# P24_AUDIO.net
KiCad netlist of a schematic drawn in Altium Designer
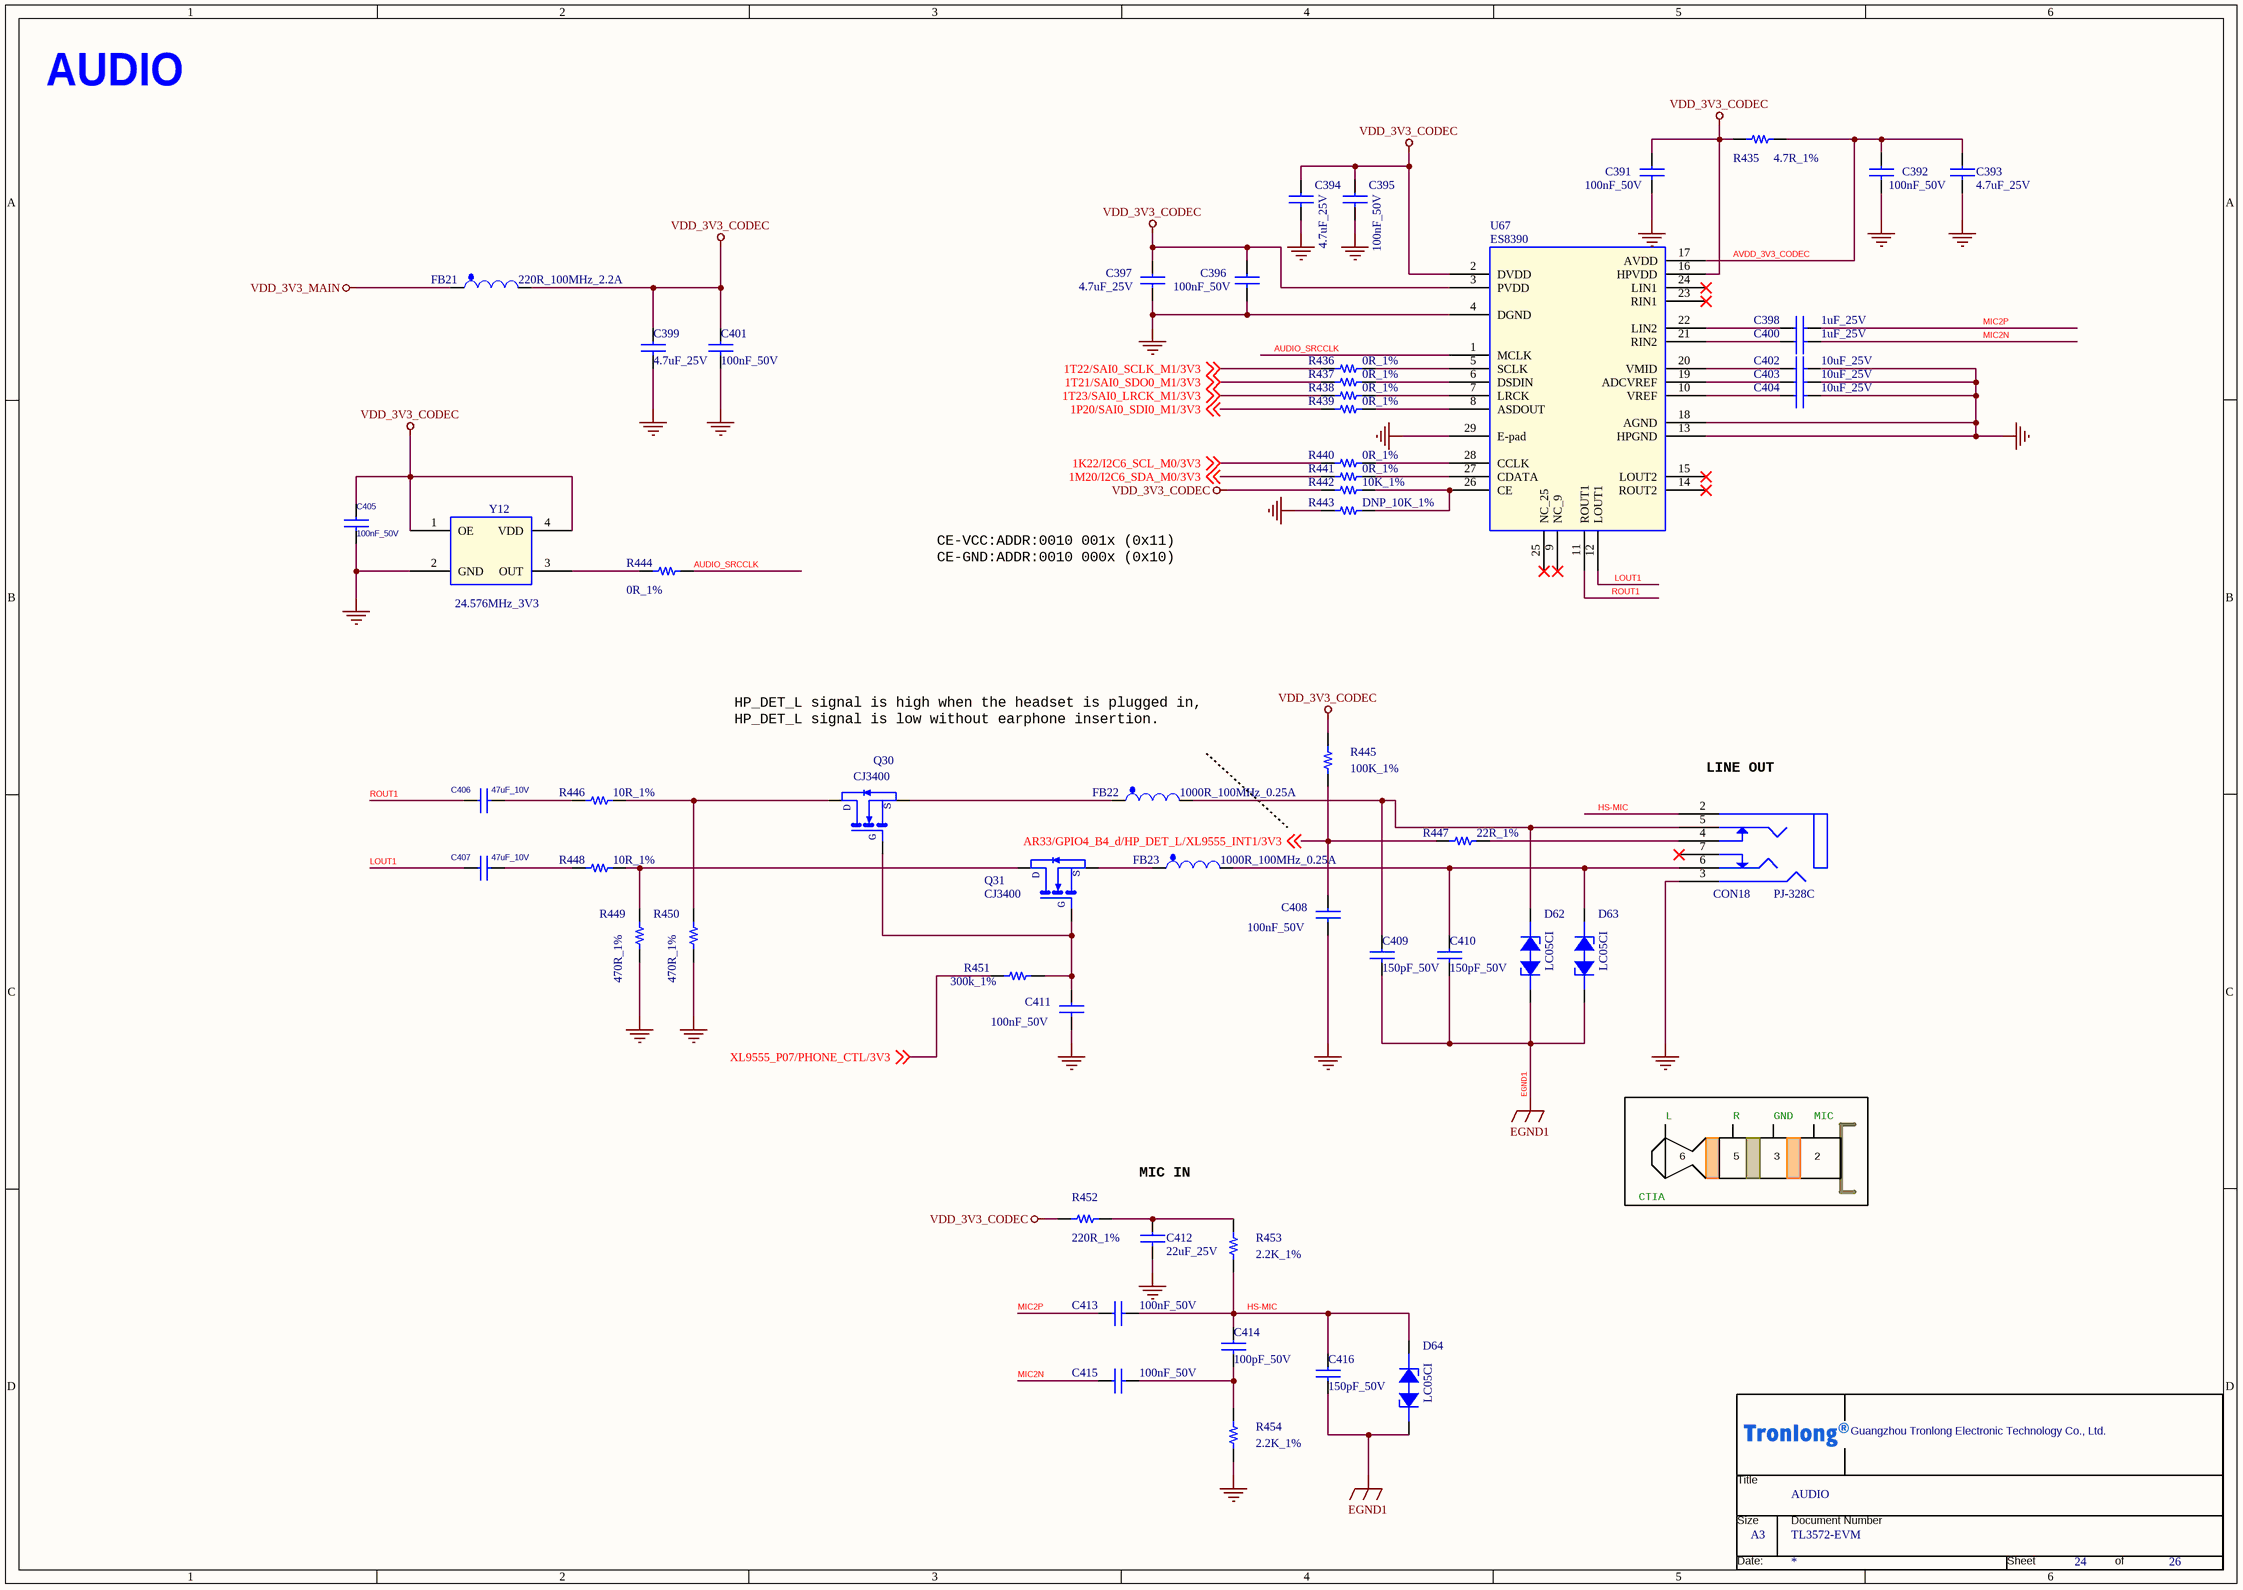
[diagram p0: P24_AUDIO.SchDoc]

(export (version "E")
  (design (tool "Eeschema 10.0.6"))
  (components
    (comp (ref "*")
      (value "TL_NEW")
      (fields
        (field (name "PAGE COUNT") "26")
        (field (name "PAGE NUMBER") "24")
        (field (name "PAGE SIZE") "A3")
        (field (name "ORGNAME") "Guangzhou Tronlong Electronic Technology Co., Ltd.")
        (field (name "TITLE") "AUDIO")
        (field (name "DOC") "TL3572-EVM")
      )
      (libsource (lib "*") (part "TL_NEW"))
    )
    (comp (ref "C391")
      (value "100nF_50V")
      (footprint "C0402")
      (description "贴片陶瓷电容,100nF,10%,50V,X7R")
      (fields
        (field (name "MANUFACTURER") "广东风华高新科技股份有限公司（FH）")
        (field (name "MANUFACTURER PARTNUMBER") "0402B104K500NT")
      )
      (libsource (lib "*") (part "CAP NP_Dup3"))
    )
    (comp (ref "C392")
      (value "100nF_50V")
      (footprint "C0402")
      (description "贴片陶瓷电容,100nF,10%,50V,X7R")
      (fields
        (field (name "MANUFACTURER PARTNUMBER") "0402B104K500NT")
        (field (name "MANUFACTURER") "广东风华高新科技股份有限公司（FH）")
      )
      (libsource (lib "*") (part "CAP NP_Dup3"))
    )
    (comp (ref "C393")
      (value "4.7uF_25V")
      (footprint "C0603")
      (description "贴片陶瓷电容,4.7uF,10%,25V,X5R")
      (fields
        (field (name "MANUFACTURER") "广东风华高新科技股份有限公司（FH）")
        (field (name "MANUFACTURER PARTNUMBER") "0603X475K250NT")
      )
      (libsource (lib "*") (part "CAP NP_Dup3"))
    )
    (comp (ref "C394")
      (value "4.7uF_25V")
      (footprint "C0603")
      (description "贴片陶瓷电容,4.7uF,10%,25V,X5R")
      (fields
        (field (name "MANUFACTURER") "广东风华高新科技股份有限公司（FH）")
        (field (name "MANUFACTURER PARTNUMBER") "0603X475K250NT")
      )
      (libsource (lib "*") (part "CAP NP_Dup3"))
    )
    (comp (ref "C395")
      (value "100nF_50V")
      (footprint "C0402")
      (description "贴片陶瓷电容,100nF,10%,50V,X7R")
      (fields
        (field (name "MANUFACTURER PARTNUMBER") "0402B104K500NT")
        (field (name "MANUFACTURER") "广东风华高新科技股份有限公司（FH）")
      )
      (libsource (lib "*") (part "CAP NP_Dup3"))
    )
    (comp (ref "C396")
      (value "100nF_50V")
      (footprint "C0402")
      (description "贴片陶瓷电容,100nF,10%,50V,X7R")
      (fields
        (field (name "MANUFACTURER") "广东风华高新科技股份有限公司（FH）")
        (field (name "MANUFACTURER PARTNUMBER") "0402B104K500NT")
      )
      (libsource (lib "*") (part "CAP NP_Dup3"))
    )
    (comp (ref "C397")
      (value "4.7uF_25V")
      (footprint "C0603")
      (description "贴片陶瓷电容,4.7uF,10%,25V,X5R")
      (fields
        (field (name "MANUFACTURER") "广东风华高新科技股份有限公司（FH）")
        (field (name "MANUFACTURER PARTNUMBER") "0603X475K250NT")
      )
      (libsource (lib "*") (part "CAP NP_Dup3"))
    )
    (comp (ref "C398")
      (value "1uF_25V")
      (footprint "C0402")
      (description "贴片陶瓷电容,1uF,10%,25V,X5R")
      (fields
        (field (name "MANUFACTURER PARTNUMBER") "0402X105K250NT")
        (field (name "MANUFACTURER") "广东风华高新科技股份有限公司（FH）")
      )
      (libsource (lib "*") (part "CAP NP_Dup3"))
    )
    (comp (ref "C399")
      (value "4.7uF_25V")
      (footprint "C0603")
      (description "贴片陶瓷电容,4.7uF,10%,25V,X5R")
      (fields
        (field (name "MANUFACTURER PARTNUMBER") "0603X475K250NT")
        (field (name "MANUFACTURER") "广东风华高新科技股份有限公司（FH）")
      )
      (libsource (lib "*") (part "CAP NP_Dup3"))
    )
    (comp (ref "C400")
      (value "1uF_25V")
      (footprint "C0402")
      (description "贴片陶瓷电容,1uF,10%,25V,X5R")
      (fields
        (field (name "MANUFACTURER PARTNUMBER") "0402X105K250NT")
        (field (name "MANUFACTURER") "广东风华高新科技股份有限公司（FH）")
      )
      (libsource (lib "*") (part "CAP NP_Dup3"))
    )
    (comp (ref "C401")
      (value "100nF_50V")
      (footprint "C0402")
      (description "贴片陶瓷电容,100nF,10%,50V,X7R")
      (fields
        (field (name "MANUFACTURER PARTNUMBER") "0402B104K500NT")
        (field (name "MANUFACTURER") "广东风华高新科技股份有限公司（FH）")
      )
      (libsource (lib "*") (part "CAP NP_Dup3"))
    )
    (comp (ref "C402")
      (value "10uF_25V")
      (footprint "C0603")
      (description "贴片陶瓷电容,10uF,20%,25V,X5R")
      (fields
        (field (name "MANUFACTURER PARTNUMBER") "0603X106M250NT")
        (field (name "MANUFACTURER") "广东风华高新科技股份有限公司（FH）")
      )
      (libsource (lib "*") (part "CAP NP_Dup3"))
    )
    (comp (ref "C403")
      (value "10uF_25V")
      (footprint "C0603")
      (description "贴片陶瓷电容,10uF,20%,25V,X5R")
      (fields
        (field (name "MANUFACTURER PARTNUMBER") "0603X106M250NT")
        (field (name "MANUFACTURER") "广东风华高新科技股份有限公司（FH）")
      )
      (libsource (lib "*") (part "CAP NP_Dup3"))
    )
    (comp (ref "C404")
      (value "10uF_25V")
      (footprint "C0603")
      (description "贴片陶瓷电容,10uF,20%,25V,X5R")
      (fields
        (field (name "MANUFACTURER") "广东风华高新科技股份有限公司（FH）")
        (field (name "MANUFACTURER PARTNUMBER") "0603X106M250NT")
      )
      (libsource (lib "*") (part "CAP NP_Dup3"))
    )
    (comp (ref "C405")
      (value "100nF_50V")
      (footprint "C0402")
      (description "贴片陶瓷电容,100nF,10%,50V,X7R")
      (fields
        (field (name "MANUFACTURER") "广东风华高新科技股份有限公司（FH）")
        (field (name "MANUFACTURER PARTNUMBER") "0402B104K500NT")
      )
      (libsource (lib "*") (part "CAP NP_Dup2"))
    )
    (comp (ref "C406")
      (value "47uF_10V")
      (footprint "C0805")
      (description "贴片陶瓷电容,47uF,20%,10V,X5R")
      (fields
        (field (name "MANUFACTURER PARTNUMBER") "0805X476M100NT")
        (field (name "MANUFACTURER") "广东风华高新科技股份有限公司（FH）")
      )
      (libsource (lib "*") (part "CAP NP_Dup3"))
    )
    (comp (ref "C407")
      (value "47uF_10V")
      (footprint "C0805")
      (description "贴片陶瓷电容,47uF,20%,10V,X5R")
      (fields
        (field (name "MANUFACTURER PARTNUMBER") "0805X476M100NT")
        (field (name "MANUFACTURER") "广东风华高新科技股份有限公司（FH）")
      )
      (libsource (lib "*") (part "CAP NP_Dup3"))
    )
    (comp (ref "C408")
      (value "100nF_50V")
      (footprint "C0402")
      (description "贴片陶瓷电容,100nF,10%,50V,X7R")
      (fields
        (field (name "MANUFACTURER PARTNUMBER") "0402B104K500NT")
        (field (name "MANUFACTURER") "广东风华高新科技股份有限公司（FH）")
      )
      (libsource (lib "*") (part "CAP NP_Dup3"))
    )
    (comp (ref "C409")
      (value "150pF_50V")
      (footprint "C0603")
      (description "贴片陶瓷电容,150pF,5%,50V,COG")
      (fields
        (field (name "MANUFACTURER") "广东风华高新科技股份有限公司（FH）")
        (field (name "MANUFACTURER PARTNUMBER") "0603CG151J500NT")
      )
      (libsource (lib "*") (part "CAP NP_Dup2"))
    )
    (comp (ref "C410")
      (value "150pF_50V")
      (footprint "C0603")
      (description "贴片陶瓷电容,150pF,5%,50V,COG")
      (fields
        (field (name "MANUFACTURER PARTNUMBER") "0603CG151J500NT")
        (field (name "MANUFACTURER") "广东风华高新科技股份有限公司（FH）")
      )
      (libsource (lib "*") (part "CAP NP_Dup2"))
    )
    (comp (ref "C411")
      (value "100nF_50V")
      (footprint "C0402")
      (description "贴片陶瓷电容,100nF,10%,50V,X7R")
      (fields
        (field (name "MANUFACTURER PARTNUMBER") "0402B104K500NT")
        (field (name "MANUFACTURER") "广东风华高新科技股份有限公司（FH）")
      )
      (libsource (lib "*") (part "CAP NP_Dup3"))
    )
    (comp (ref "C412")
      (value "22uF_25V")
      (footprint "C0805")
      (description "贴片陶瓷电容,22uF,20%,25V,X5R")
      (fields
        (field (name "MANUFACTURER") "广东风华高新科技股份有限公司（FH）")
        (field (name "MANUFACTURER PARTNUMBER") "0805X226M250NT")
      )
      (libsource (lib "*") (part "CAP NP_Dup3"))
    )
    (comp (ref "C413")
      (value "100nF_50V")
      (footprint "C0402")
      (description "贴片陶瓷电容,100nF,10%,50V,X7R")
      (fields
        (field (name "VOLTAGE") "50V")
        (field (name "TOLERANCE") "10%")
        (field (name "CREATED BY") "JJJ")
      )
      (libsource (lib "*") (part "CAP NP_Dup3"))
    )
    (comp (ref "C414")
      (value "100pF_50V")
      (footprint "C0402")
      (description "贴片陶瓷电容,100pF,5%,50V,COG")
      (fields
        (field (name "MANUFACTURER PARTNUMBER") "0402CG101J500NT")
        (field (name "MANUFACTURER") "广东风华高新科技股份有限公司（FH）")
        (field (name "CREATED BY") "JJJ")
      )
      (libsource (lib "*") (part "CAP NP_Dup3"))
    )
    (comp (ref "C415")
      (value "100nF_50V")
      (footprint "C0402")
      (description "贴片陶瓷电容,100nF,10%,50V,X7R")
      (fields
        (field (name "VOLTAGE") "50V")
        (field (name "TOLERANCE") "10%")
        (field (name "CREATED BY") "JJJ")
      )
      (libsource (lib "*") (part "CAP NP_Dup3"))
    )
    (comp (ref "C416")
      (value "150pF_50V")
      (footprint "C0603")
      (description "贴片陶瓷电容,150pF,5%,50V,COG")
      (fields
        (field (name "MANUFACTURER PARTNUMBER") "0603CG151J500NT")
        (field (name "MANUFACTURER") "广东风华高新科技股份有限公司（FH）")
      )
      (libsource (lib "*") (part "CAP NP_Dup2"))
    )
    (comp (ref "CON18")
      (value "PJ-328C")
      (footprint "PJ-328C")
      (description "插件音频连接器,孔径3.5mm,黑色")
      (fields (field (name "MANUFACTURER") "深圳市金航标电子有限公司(kinghelm)"))
      (libsource (lib "*") (part "PJ-328C_0"))
    )
    (comp (ref "D62")
      (value "LC05CI")
      (footprint "SOD323")
      (description "TVS二极管,VRWM=5V,VBR=6V,一组,双向,30KV,30KV")
      (fields (field (name "MANUFACTURER") "上海雷卯电子科技有限公司（Leiditech）"))
      (libsource (lib "*") (part "DIODE BREAKDOWN_2"))
    )
    (comp (ref "D63")
      (value "LC05CI")
      (footprint "SOD323")
      (description "TVS二极管,VRWM=5V,VBR=6V,一组,双向,30KV,30KV")
      (fields (field (name "MANUFACTURER") "上海雷卯电子科技有限公司（Leiditech）"))
      (libsource (lib "*") (part "DIODE BREAKDOWN_2"))
    )
    (comp (ref "D64")
      (value "LC05CI")
      (footprint "SOD323")
      (description "TVS二极管,VRWM=5V,VBR=6V,一组,双向,30KV,30KV")
      (fields (field (name "MANUFACTURER") "上海雷卯电子科技有限公司（Leiditech）"))
      (libsource (lib "*") (part "DIODE BREAKDOWN_2"))
    )
    (comp (ref "FB21")
      (value "220R_100MHz_2.2A")
      (footprint "L0603")
      (description "磁珠,50mΩ,2.2A,220R@100MHz")
      (fields
        (field (name "PART NUMBER") "647-01-3069")
        (field (name "MANUFACTURER PARTNUMBER") "UPZ1608U221-2R2TF")
      )
      (libsource (lib "*") (part "FB_0"))
    )
    (comp (ref "FB22")
      (value "1000R_100MHz_0.25A")
      (footprint "L0402")
      (description "磁珠,900mΩ,0.25A,1000R@100MHz")
      (fields
        (field (name "MANUFACTURER") "广东风华高新科技股份有限公司(FH)")
        (field (name "MANUFACTURER PARTNUMBER") "CBW100505U102T")
      )
      (libsource (lib "*") (part "FB_0"))
    )
    (comp (ref "FB23")
      (value "1000R_100MHz_0.25A")
      (footprint "L0402")
      (description "磁珠,900mΩ,0.25A,1000R@100MHz")
      (fields
        (field (name "PART NUMBER") "647-01-3069")
        (field (name "MANUFACTURER PARTNUMBER") "CBW100505U102T")
      )
      (libsource (lib "*") (part "FB_0"))
    )
    (comp (ref "Q30")
      (value "CJ3400")
      (footprint "SOT23-3")
      (description "MOSFET,N沟道,VDSS=30V,VGSS=±12V,ID=5.8A,PD=0.35W,VGS(th)=1.4V")
      (fields (field (name "MANUFACTURER") "江苏长晶科技股份有限公司（JSCJ）"))
      (libsource (lib "*") (part "MMBT3904/SOT_1"))
    )
    (comp (ref "Q31")
      (value "CJ3400")
      (footprint "SOT23-3")
      (description "MOSFET,N沟道,VDSS=30V,VGSS=±12V,ID=5.8A,PD=0.35W,VGS(th)=1.4V")
      (fields (field (name "MANUFACTURER") "江苏长晶科技股份有限公司（JSCJ）"))
      (libsource (lib "*") (part "MMBT3904/SOT_1"))
    )
    (comp (ref "R435")
      (value "4.7R_1%")
      (footprint "R0603")
      (description "/")
      (fields
        (field (name "MANUFACTURER PARTNUMBER") "4.7R,±1%,R0603,≥1/10W")
        (field (name "MANUFACTURER") "广州创龙")
      )
      (libsource (lib "*") (part "Resistor_Dup4"))
    )
    (comp (ref "R436")
      (value "0R_1%")
      (footprint "R0402")
      (description "贴片电阻,0R,±1%,1/16W")
      (fields
        (field (name "MANUFACTURER") "广东风华高新科技股份有限公司（FH）")
        (field (name "MANUFACTURER PARTNUMBER") "RC-02000FT")
      )
      (libsource (lib "*") (part "Resistor_Dup4"))
    )
    (comp (ref "R437")
      (value "0R_1%")
      (footprint "R0402")
      (description "贴片电阻,0R,±1%,1/16W")
      (fields
        (field (name "MANUFACTURER") "广东风华高新科技股份有限公司（FH）")
        (field (name "MANUFACTURER PARTNUMBER") "RC-02000FT")
      )
      (libsource (lib "*") (part "Resistor_Dup4"))
    )
    (comp (ref "R438")
      (value "0R_1%")
      (footprint "R0402")
      (description "贴片电阻,0R,±1%,1/16W")
      (fields (field (name "TOLERANCE") "5%") (field (name "MANUFACTURER PARTNUMBER") "RC-02000FT"))
      (libsource (lib "*") (part "Resistor_Dup4"))
    )
    (comp (ref "R439")
      (value "0R_1%")
      (footprint "R0402")
      (description "贴片电阻,0R,±1%,1/16W")
      (fields (field (name "TOLERANCE") "5%") (field (name "MANUFACTURER PARTNUMBER") "RC-02000FT"))
      (libsource (lib "*") (part "Resistor_Dup4"))
    )
    (comp (ref "R440")
      (value "0R_1%")
      (footprint "R0402")
      (description "贴片电阻,0R,±1%,1/16W")
      (fields (field (name "TOLERANCE") "5%") (field (name "MANUFACTURER PARTNUMBER") "RC-02000FT"))
      (libsource (lib "*") (part "Resistor_Dup4"))
    )
    (comp (ref "R441")
      (value "0R_1%")
      (footprint "R0402")
      (description "贴片电阻,0R,±1%,1/16W")
      (fields (field (name "TOLERANCE") "5%") (field (name "MANUFACTURER PARTNUMBER") "RC-02000FT"))
      (libsource (lib "*") (part "Resistor_Dup4"))
    )
    (comp (ref "R442")
      (value "10K_1%")
      (footprint "R0402")
      (description "贴片电阻,10K,±1%,1/16W")
      (fields
        (field (name "MANUFACTURER") "广东风华高新科技股份有限公司（FH）")
        (field (name "MANUFACTURER PARTNUMBER") "RC-02K1002FT")
      )
      (libsource (lib "*") (part "Resistor_Dup4"))
    )
    (comp (ref "R443")
      (value "DNP_10K_1%")
      (footprint "R0402")
      (description "贴片电阻,10K,±1%,1/16W")
      (fields (field (name "TOLERANCE") "5%") (field (name "MANUFACTURER PARTNUMBER") "RC-02K1002FT"))
      (libsource (lib "*") (part "Resistor_Dup4"))
    )
    (comp (ref "R444")
      (value "0R_1%")
      (footprint "R0603")
      (description "贴片电阻,0R,±1%,1/10W")
      (fields
        (field (name "MANUFACTURER") "广东风华高新科技股份有限公司（FH）")
        (field (name "MANUFACTURER PARTNUMBER") "RS-03000FT")
      )
      (libsource (lib "*") (part "Resistor_Dup3"))
    )
    (comp (ref "R445")
      (value "100K_1%")
      (footprint "R0402")
      (description "RC0402FR-07100KL,0402WGF1003TCE")
      (fields
        (field (name "MANUFACTURER") "广州创龙")
        (field (name "MANUFACTURER PARTNUMBER") "100K,±1%,R0402,≥1/16W")
      )
      (libsource (lib "*") (part "Resistor_Dup4"))
    )
    (comp (ref "R446")
      (value "10R_1%")
      (footprint "R0603")
      (description "贴片电阻,10R,±1%,1/10W")
      (fields
        (field (name "MANUFACTURER") "广东风华高新科技股份有限公司（FH）")
        (field (name "MANUFACTURER PARTNUMBER") "RS-03K10R0FT")
      )
      (libsource (lib "*") (part "Resistor_Dup4"))
    )
    (comp (ref "R447")
      (value "22R_1%")
      (footprint "R0402")
      (description "贴片电阻,22R,±1%,1/16W")
      (fields
        (field (name "MANUFACTURER") "广东风华高新科技股份有限公司（FH）")
        (field (name "MANUFACTURER PARTNUMBER") "RC-02K22R0FT")
      )
      (libsource (lib "*") (part "Resistor_Dup4"))
    )
    (comp (ref "R448")
      (value "10R_1%")
      (footprint "R0603")
      (description "贴片电阻,10R,±1%,1/10W")
      (fields (field (name "TOLERANCE") "5%") (field (name "MANUFACTURER PARTNUMBER") "RS-03K10R0FT"))
      (libsource (lib "*") (part "Resistor_Dup4"))
    )
    (comp (ref "R449")
      (value "470R_1%")
      (footprint "R0603")
      (description "贴片电阻,470R,±1%,1/10W")
      (fields (field (name "TOLERANCE") "5%") (field (name "MANUFACTURER PARTNUMBER") "RS-03K4700FT"))
      (libsource (lib "*") (part "Resistor_Dup4"))
    )
    (comp (ref "R450")
      (value "470R_1%")
      (footprint "R0603")
      (description "贴片电阻,470R,±1%,1/10W")
      (fields (field (name "TOLERANCE") "5%") (field (name "MANUFACTURER PARTNUMBER") "RS-03K4700FT"))
      (libsource (lib "*") (part "Resistor_Dup4"))
    )
    (comp (ref "R451")
      (value "300k_1%")
      (footprint "R0402")
      (description "贴片电阻,300K,±1%,1/16W")
      (fields
        (field (name "MANUFACTURER") "广东风华高新科技股份有限公司（FH）")
        (field (name "MANUFACTURER PARTNUMBER") "RC-02K3003FT")
      )
      (libsource (lib "*") (part "Resistor_Dup4"))
    )
    (comp (ref "R452")
      (value "220R_1%")
      (footprint "R0603")
      (description "贴片电阻,220R,±1%,1/10W")
      (fields (field (name "TOLERANCE") "5%") (field (name "MANUFACTURER PARTNUMBER") "RS-03K2200FT"))
      (libsource (lib "*") (part "Resistor_Dup4"))
    )
    (comp (ref "R453")
      (value "2.2K_1%")
      (footprint "R0603")
      (description "贴片电阻,2.2K,±1%,1/10W")
      (fields (field (name "TOLERANCE") "5%") (field (name "MANUFACTURER PARTNUMBER") "RS-03K2201FT"))
      (libsource (lib "*") (part "Resistor_Dup4"))
    )
    (comp (ref "R454")
      (value "2.2K_1%")
      (footprint "R0603")
      (description "贴片电阻,2.2K,±1%,1/10W")
      (fields (field (name "TOLERANCE") "5%") (field (name "MANUFACTURER PARTNUMBER") "RS-03K2201FT"))
      (libsource (lib "*") (part "Resistor_Dup4"))
    )
    (comp (ref "U67")
      (value "ES8390")
      (footprint "QFN28_ES8388")
      (description "立体声音频编解码器")
      (fields (field (name "MANUFACTURER") "苏州顺芯半导体有限公司（Everest）") (field (name "CREATED BY") "JJJ"))
      (libsource (lib "*") (part "Amplifier_ES8388"))
    )
    (comp (ref "Y12")
      (value "24.576MHz_3V3")
      (footprint "SMD_3225")
      (description "四脚有源晶振,24.576MHz,3.3V,CMOS,±30ppm")
      (fields
        (field (name "MANUFACTURER") "深圳市星通时频电子有限公司（SCTF）")
        (field (name "MFR_PART_NUMBER") "S3M24.576B20F30TNN")
      )
      (libsource (lib "*") (part "CMX309"))
    )
  )
  (nets
    (net (code "1") (name "/AUDIO_SRCCLK") (class "Default")
      (node (ref "R444") (pin "2") (pinfunction "2_2") (pintype "passive"))
      (node (ref "U67") (pin "1") (pinfunction "MCLK_1") (pintype "passive"))
    )
    (net (code "2") (name "/AVDD_3V3_CODEC") (class "Default")
      (node (ref "C392") (pin "1") (pinfunction "1_1") (pintype "passive"))
      (node (ref "C393") (pin "1") (pinfunction "1_1") (pintype "passive"))
      (node (ref "R435") (pin "1") (pinfunction "1_1") (pintype "passive"))
      (node (ref "U67") (pin "17") (pinfunction "AVDD_17") (pintype "passive"))
    )
    (net (code "3") (name "/HS-MIC") (class "Default")
      (node (ref "C413") (pin "2") (pinfunction "2_2") (pintype "passive"))
      (node (ref "C414") (pin "1") (pinfunction "1_1") (pintype "passive"))
      (node (ref "C416") (pin "1") (pinfunction "1_1") (pintype "passive"))
      (node (ref "CON18") (pin "2") (pinfunction "MIC_2") (pintype "passive"))
      (node (ref "D64") (pin "1") (pinfunction "ANODE1_1") (pintype "passive"))
      (node (ref "R453") (pin "2") (pinfunction "2_2") (pintype "passive"))
    )
    (net (code "4") (name "/LOUT1") (class "Default")
      (node (ref "C407") (pin "1") (pinfunction "1_1") (pintype "passive"))
      (node (ref "U67") (pin "12") (pinfunction "LOUT1_12") (pintype "passive"))
    )
    (net (code "5") (name "/MIC2N") (class "Default")
      (node (ref "C400") (pin "2") (pinfunction "2_2") (pintype "passive"))
      (node (ref "C415") (pin "1") (pinfunction "1_1") (pintype "passive"))
    )
    (net (code "6") (name "/MIC2P") (class "Default")
      (node (ref "C398") (pin "2") (pinfunction "2_2") (pintype "passive"))
      (node (ref "C413") (pin "1") (pinfunction "1_1") (pintype "passive"))
    )
    (net (code "7") (name "/ROUT1") (class "Default")
      (node (ref "C406") (pin "1") (pinfunction "1_1") (pintype "passive"))
      (node (ref "U67") (pin "11") (pinfunction "ROUT1_11") (pintype "passive"))
    )
    (net (code "8") (name "1K22{slash}I2C6_SCL_M0{slash}3V3") (class "Default")
      (node (ref "R440") (pin "1") (pinfunction "1_1") (pintype "passive"))
    )
    (net (code "9") (name "1M20{slash}I2C6_SDA_M0{slash}3V3") (class "Default")
      (node (ref "R441") (pin "1") (pinfunction "1_1") (pintype "passive"))
    )
    (net (code "10") (name "1P20{slash}SAI0_SDI0_M1{slash}3V3") (class "Default")
      (node (ref "R439") (pin "1") (pinfunction "1_1") (pintype "passive"))
    )
    (net (code "11") (name "1T21{slash}SAI0_SDO0_M1{slash}3V3") (class "Default")
      (node (ref "R437") (pin "1") (pinfunction "1_1") (pintype "passive"))
    )
    (net (code "12") (name "1T22{slash}SAI0_SCLK_M1{slash}3V3") (class "Default")
      (node (ref "R436") (pin "1") (pinfunction "1_1") (pintype "passive"))
    )
    (net (code "13") (name "1T23{slash}SAI0_LRCK_M1{slash}3V3") (class "Default")
      (node (ref "R438") (pin "1") (pinfunction "1_1") (pintype "passive"))
    )
    (net (code "14") (name "AR33{slash}GPIO4_B4_d{slash}HP_DET_L{slash}XL9555_INT1{slash}3V3") (class "Default")
      (node (ref "C408") (pin "1") (pinfunction "1_1") (pintype "passive"))
      (node (ref "R445") (pin "2") (pinfunction "2_2") (pintype "passive"))
      (node (ref "R447") (pin "1") (pinfunction "1_1") (pintype "passive"))
    )
    (net (code "15") (name "EGND1") (class "Default")
      (node (ref "C409") (pin "2") (pinfunction "2_2") (pintype "passive"))
      (node (ref "C410") (pin "2") (pinfunction "2_2") (pintype "passive"))
      (node (ref "C416") (pin "2") (pinfunction "2_2") (pintype "passive"))
      (node (ref "D62") (pin "2") (pinfunction "CATHODE2_2") (pintype "passive"))
      (node (ref "D63") (pin "2") (pinfunction "CATHODE2_2") (pintype "passive"))
      (node (ref "D64") (pin "2") (pinfunction "CATHODE2_2") (pintype "passive"))
    )
    (net (code "16") (name "GND") (class "Default")
      (node (ref "C391") (pin "2") (pinfunction "2_2") (pintype "passive"))
      (node (ref "C392") (pin "2") (pinfunction "2_2") (pintype "passive"))
      (node (ref "C393") (pin "2") (pinfunction "2_2") (pintype "passive"))
      (node (ref "C394") (pin "2") (pinfunction "2_2") (pintype "passive"))
      (node (ref "C395") (pin "2") (pinfunction "2_2") (pintype "passive"))
      (node (ref "C396") (pin "2") (pinfunction "2_2") (pintype "passive"))
      (node (ref "C397") (pin "2") (pinfunction "2_2") (pintype "passive"))
      (node (ref "C399") (pin "2") (pinfunction "2_2") (pintype "passive"))
      (node (ref "C401") (pin "2") (pinfunction "2_2") (pintype "passive"))
      (node (ref "C402") (pin "2") (pinfunction "2_2") (pintype "passive"))
      (node (ref "C403") (pin "2") (pinfunction "2_2") (pintype "passive"))
      (node (ref "C404") (pin "2") (pinfunction "2_2") (pintype "passive"))
      (node (ref "C405") (pin "2") (pinfunction "2_2") (pintype "passive"))
      (node (ref "C408") (pin "2") (pinfunction "2_2") (pintype "passive"))
      (node (ref "C411") (pin "2") (pinfunction "2_2") (pintype "passive"))
      (node (ref "C412") (pin "2") (pinfunction "2_2") (pintype "passive"))
      (node (ref "CON18") (pin "3") (pinfunction "GND_3") (pintype "passive"))
      (node (ref "R443") (pin "1") (pinfunction "1_1") (pintype "passive"))
      (node (ref "R449") (pin "1") (pinfunction "1_1") (pintype "passive"))
      (node (ref "R450") (pin "1") (pinfunction "1_1") (pintype "passive"))
      (node (ref "R454") (pin "2") (pinfunction "2_2") (pintype "passive"))
      (node (ref "U67") (pin "13") (pinfunction "HPGND_13") (pintype "power_in"))
      (node (ref "U67") (pin "18") (pinfunction "AGND_18") (pintype "power_in"))
      (node (ref "U67") (pin "29") (pinfunction "E-pad_29") (pintype "passive"))
      (node (ref "U67") (pin "4") (pinfunction "DGND_4") (pintype "passive"))
      (node (ref "Y12") (pin "2") (pinfunction "GND_2") (pintype "passive"))
    )
    (net (code "17") (name "Net-(C406-Pad2)") (class "Default")
      (node (ref "C406") (pin "2") (pinfunction "2_2") (pintype "passive"))
      (node (ref "R446") (pin "1") (pinfunction "1_1") (pintype "passive"))
    )
    (net (code "18") (name "Net-(C407-Pad2)") (class "Default")
      (node (ref "C407") (pin "2") (pinfunction "2_2") (pintype "passive"))
      (node (ref "R448") (pin "1") (pinfunction "1_1") (pintype "passive"))
    )
    (net (code "19") (name "Net-(C412-Pad1)") (class "Default")
      (node (ref "C412") (pin "1") (pinfunction "1_1") (pintype "passive"))
      (node (ref "R452") (pin "2") (pinfunction "2_2") (pintype "passive"))
      (node (ref "R453") (pin "1") (pinfunction "1_1") (pintype "passive"))
    )
    (net (code "20") (name "Net-(C414-Pad2)") (class "Default")
      (node (ref "C414") (pin "2") (pinfunction "2_2") (pintype "passive"))
      (node (ref "C415") (pin "2") (pinfunction "2_2") (pintype "passive"))
      (node (ref "R454") (pin "1") (pinfunction "1_1") (pintype "passive"))
    )
    (net (code "21") (name "Net-(CON18-DETR)") (class "Default")
      (node (ref "CON18") (pin "4") (pinfunction "DETR_4") (pintype "passive"))
      (node (ref "R447") (pin "2") (pinfunction "2_2") (pintype "passive"))
    )
    (net (code "22") (name "Net-(CON18-L)") (class "Default")
      (node (ref "C410") (pin "1") (pinfunction "1_1") (pintype "passive"))
      (node (ref "CON18") (pin "6") (pinfunction "L_6") (pintype "passive"))
      (node (ref "D63") (pin "1") (pinfunction "ANODE1_1") (pintype "passive"))
      (node (ref "FB23") (pin "2") (pinfunction "2_2") (pintype "passive"))
    )
    (net (code "23") (name "Net-(CON18-R)") (class "Default")
      (node (ref "C409") (pin "1") (pinfunction "1_1") (pintype "passive"))
      (node (ref "CON18") (pin "5") (pinfunction "R_5") (pintype "passive"))
      (node (ref "D62") (pin "1") (pinfunction "ANODE1_1") (pintype "passive"))
      (node (ref "FB22") (pin "2") (pinfunction "2_2") (pintype "passive"))
    )
    (net (code "24") (name "Net-(Q30-B)") (class "Default")
      (node (ref "C411") (pin "1") (pinfunction "1_1") (pintype "passive"))
      (node (ref "Q30") (pin "1") (pinfunction "B_1") (pintype "passive"))
      (node (ref "Q31") (pin "1") (pinfunction "B_1") (pintype "passive"))
      (node (ref "R451") (pin "1") (pinfunction "1_1") (pintype "passive"))
    )
    (net (code "25") (name "Net-(Q30-C)") (class "Default")
      (node (ref "Q30") (pin "3") (pinfunction "C_3") (pintype "passive"))
      (node (ref "R446") (pin "2") (pinfunction "2_2") (pintype "passive"))
      (node (ref "R450") (pin "2") (pinfunction "2_2") (pintype "passive"))
    )
    (net (code "26") (name "Net-(Q30-E)") (class "Default")
      (node (ref "FB22") (pin "1") (pinfunction "1_1") (pintype "passive"))
      (node (ref "Q30") (pin "2") (pinfunction "E_2") (pintype "passive"))
    )
    (net (code "27") (name "Net-(Q31-C)") (class "Default")
      (node (ref "Q31") (pin "3") (pinfunction "C_3") (pintype "passive"))
      (node (ref "R448") (pin "2") (pinfunction "2_2") (pintype "passive"))
      (node (ref "R449") (pin "2") (pinfunction "2_2") (pintype "passive"))
    )
    (net (code "28") (name "Net-(Q31-E)") (class "Default")
      (node (ref "FB23") (pin "1") (pinfunction "1_1") (pintype "passive"))
      (node (ref "Q31") (pin "2") (pinfunction "E_2") (pintype "passive"))
    )
    (net (code "29") (name "Net-(U67-ADCVREF)") (class "Default")
      (node (ref "C403") (pin "1") (pinfunction "1_1") (pintype "passive"))
      (node (ref "U67") (pin "19") (pinfunction "ADCVREF_19") (pintype "passive"))
    )
    (net (code "30") (name "Net-(U67-ASDOUT)") (class "Default")
      (node (ref "R439") (pin "2") (pinfunction "2_2") (pintype "passive"))
      (node (ref "U67") (pin "8") (pinfunction "ASDOUT_8") (pintype "passive"))
    )
    (net (code "31") (name "Net-(U67-CCLK)") (class "Default")
      (node (ref "R440") (pin "2") (pinfunction "2_2") (pintype "passive"))
      (node (ref "U67") (pin "28") (pinfunction "CCLK_28") (pintype "passive"))
    )
    (net (code "32") (name "Net-(U67-CDATA)") (class "Default")
      (node (ref "R441") (pin "2") (pinfunction "2_2") (pintype "passive"))
      (node (ref "U67") (pin "27") (pinfunction "CDATA_27") (pintype "passive"))
    )
    (net (code "33") (name "Net-(U67-CE)") (class "Default")
      (node (ref "R442") (pin "2") (pinfunction "2_2") (pintype "passive"))
      (node (ref "R443") (pin "2") (pinfunction "2_2") (pintype "passive"))
      (node (ref "U67") (pin "26") (pinfunction "CE_26") (pintype "passive"))
    )
    (net (code "34") (name "Net-(U67-DSDIN)") (class "Default")
      (node (ref "R437") (pin "2") (pinfunction "2_2") (pintype "passive"))
      (node (ref "U67") (pin "6") (pinfunction "DSDIN_6") (pintype "passive"))
    )
    (net (code "35") (name "Net-(U67-LIN2)") (class "Default")
      (node (ref "C398") (pin "1") (pinfunction "1_1") (pintype "passive"))
      (node (ref "U67") (pin "22") (pinfunction "LIN2_22") (pintype "passive"))
    )
    (net (code "36") (name "Net-(U67-LRCK)") (class "Default")
      (node (ref "R438") (pin "2") (pinfunction "2_2") (pintype "passive"))
      (node (ref "U67") (pin "7") (pinfunction "LRCK_7") (pintype "passive"))
    )
    (net (code "37") (name "Net-(U67-RIN2)") (class "Default")
      (node (ref "C400") (pin "1") (pinfunction "1_1") (pintype "passive"))
      (node (ref "U67") (pin "21") (pinfunction "RIN2_21") (pintype "passive"))
    )
    (net (code "38") (name "Net-(U67-SCLK)") (class "Default")
      (node (ref "R436") (pin "2") (pinfunction "2_2") (pintype "passive"))
      (node (ref "U67") (pin "5") (pinfunction "SCLK_5") (pintype "passive"))
    )
    (net (code "39") (name "Net-(U67-VMID)") (class "Default")
      (node (ref "C402") (pin "1") (pinfunction "1_1") (pintype "passive"))
      (node (ref "U67") (pin "20") (pinfunction "VMID_20") (pintype "passive"))
    )
    (net (code "40") (name "Net-(U67-VREF)") (class "Default")
      (node (ref "C404") (pin "1") (pinfunction "1_1") (pintype "passive"))
      (node (ref "U67") (pin "10") (pinfunction "VREF_10") (pintype "passive"))
    )
    (net (code "41") (name "Net-(Y12-OUT)") (class "Default")
      (node (ref "R444") (pin "1") (pinfunction "1_1") (pintype "passive"))
      (node (ref "Y12") (pin "3") (pinfunction "OUT_3") (pintype "passive"))
    )
    (net (code "42") (name "VDD_3V3_CODEC") (class "Default")
      (node (ref "C391") (pin "1") (pinfunction "1_1") (pintype "passive"))
      (node (ref "C394") (pin "1") (pinfunction "1_1") (pintype "passive"))
      (node (ref "C395") (pin "1") (pinfunction "1_1") (pintype "passive"))
      (node (ref "C396") (pin "1") (pinfunction "1_1") (pintype "passive"))
      (node (ref "C397") (pin "1") (pinfunction "1_1") (pintype "passive"))
      (node (ref "C399") (pin "1") (pinfunction "1_1") (pintype "passive"))
      (node (ref "C401") (pin "1") (pinfunction "1_1") (pintype "passive"))
      (node (ref "C405") (pin "1") (pinfunction "1_1") (pintype "passive"))
      (node (ref "FB21") (pin "2") (pinfunction "2_2") (pintype "passive"))
      (node (ref "R435") (pin "2") (pinfunction "2_2") (pintype "passive"))
      (node (ref "R442") (pin "1") (pinfunction "1_1") (pintype "passive"))
      (node (ref "R445") (pin "1") (pinfunction "1_1") (pintype "passive"))
      (node (ref "R452") (pin "1") (pinfunction "1_1") (pintype "passive"))
      (node (ref "U67") (pin "16") (pinfunction "HPVDD_16") (pintype "passive"))
      (node (ref "U67") (pin "2") (pinfunction "DVDD_2") (pintype "passive"))
      (node (ref "U67") (pin "3") (pinfunction "PVDD_3") (pintype "passive"))
      (node (ref "Y12") (pin "1") (pinfunction "OE_1") (pintype "passive"))
      (node (ref "Y12") (pin "4") (pinfunction "VDD_4") (pintype "passive"))
    )
    (net (code "43") (name "VDD_3V3_MAIN") (class "Default")
      (node (ref "FB21") (pin "1") (pinfunction "1_1") (pintype "passive"))
    )
    (net (code "44") (name "XL9555_P07{slash}PHONE_CTL{slash}3V3") (class "Default")
      (node (ref "R451") (pin "2") (pinfunction "2_2") (pintype "passive"))
    )
    (net (code "45") (name "unconnected-(CON18-DETL-Pad7)") (class "Default")
      (node (ref "CON18") (pin "7") (pinfunction "DETL_7") (pintype "passive+no_connect"))
    )
    (net (code "46") (name "unconnected-(U67-LIN1-Pad24)") (class "Default")
      (node (ref "U67") (pin "24") (pinfunction "LIN1_24") (pintype "passive+no_connect"))
    )
    (net (code "47") (name "unconnected-(U67-LOUT2-Pad15)") (class "Default")
      (node (ref "U67") (pin "15") (pinfunction "LOUT2_15") (pintype "passive+no_connect"))
    )
    (net (code "48") (name "unconnected-(U67-NC_9-Pad9)") (class "Default")
      (node (ref "U67") (pin "9") (pinfunction "NC_9_9") (pintype "passive+no_connect"))
    )
    (net (code "49") (name "unconnected-(U67-NC_25-Pad25)") (class "Default")
      (node (ref "U67") (pin "25") (pinfunction "NC_25_25") (pintype "passive+no_connect"))
    )
    (net (code "50") (name "unconnected-(U67-RIN1-Pad23)") (class "Default")
      (node (ref "U67") (pin "23") (pinfunction "RIN1_23") (pintype "passive+no_connect"))
    )
    (net (code "51") (name "unconnected-(U67-ROUT2-Pad14)") (class "Default")
      (node (ref "U67") (pin "14") (pinfunction "ROUT2_14") (pintype "passive+no_connect"))
    )
  )
)
